# ECG.net
KiCad netlist of a schematic drawn in EAGLE
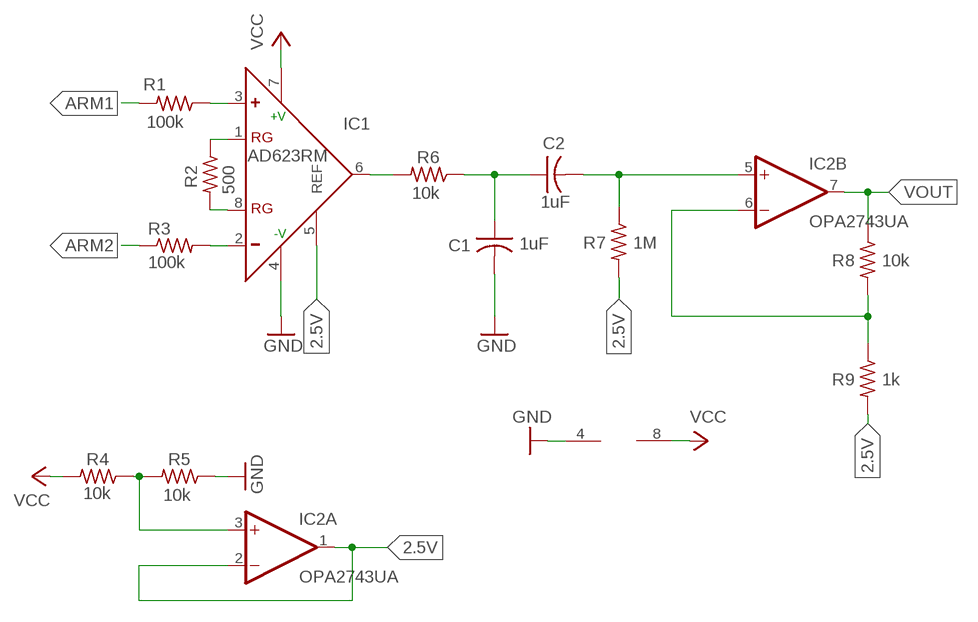
[diagram p0: schematic, sheet 1]

(export (version "E")
  (design (tool "Eeschema 10.0.6"))
  (components
    (comp (ref "C1")
      (value "1uF")
      (footprint "eagle-import:C0805")
      (libsource (lib "eagle-import") (part "C-USC0805"))
    )
    (comp (ref "C2")
      (value "1uF")
      (footprint "eagle-import:C0805")
      (libsource (lib "eagle-import") (part "C-USC0805"))
    )
    (comp (ref "IC1")
      (value "AD623RM")
      (footprint "eagle-import:MSOP08")
      (fields (field (name "MPN") "AD623ARMZ"))
      (libsource (lib "eagle-import") (part "AD623RM"))
    )
    (comp (ref "IC2")
      (value "OPA2743UA")
      (footprint "eagle-import:SOIC8")
      (libsource (lib "eagle-import") (part "OPA2743UA"))
    )
    (comp (ref "R1")
      (value "100k")
      (footprint "eagle-import:R0805")
      (libsource (lib "eagle-import") (part "R-US_R0805"))
    )
    (comp (ref "R2")
      (value "500")
      (footprint "eagle-import:R0805")
      (libsource (lib "eagle-import") (part "R-US_R0805"))
    )
    (comp (ref "R3")
      (value "100k")
      (footprint "eagle-import:R0805")
      (libsource (lib "eagle-import") (part "R-US_R0805"))
    )
    (comp (ref "R4")
      (value "10k")
      (footprint "eagle-import:R0805")
      (libsource (lib "eagle-import") (part "R-US_R0805"))
    )
    (comp (ref "R5")
      (value "10k")
      (footprint "eagle-import:R0805")
      (libsource (lib "eagle-import") (part "R-US_R0805"))
    )
    (comp (ref "R6")
      (value "10k")
      (footprint "eagle-import:R0805")
      (libsource (lib "eagle-import") (part "R-US_R0805"))
    )
    (comp (ref "R7")
      (value "1M")
      (footprint "eagle-import:R0805")
      (libsource (lib "eagle-import") (part "R-US_R0805"))
    )
    (comp (ref "R8")
      (value "10k")
      (footprint "eagle-import:R0805")
      (libsource (lib "eagle-import") (part "R-US_R0805"))
    )
    (comp (ref "R9")
      (value "1k")
      (footprint "eagle-import:R0805")
      (libsource (lib "eagle-import") (part "R-US_R0805"))
    )
  )
  (nets
    (net (code "1") (name "2.5V") (class "Default")
      (node (ref "IC1") (pin "5") (pinfunction "REF_5") (pintype "passive"))
      (node (ref "IC2") (pin "1") (pinfunction "OUT_1") (pintype "output"))
      (node (ref "IC2") (pin "2") (pinfunction "-IN_2") (pintype "input"))
      (node (ref "R7") (pin "2") (pinfunction "2_2") (pintype "passive"))
      (node (ref "R9") (pin "2") (pinfunction "2_2") (pintype "passive"))
    )
    (net (code "2") (name "ARM1") (class "Default")
      (node (ref "R1") (pin "2") (pinfunction "2_2") (pintype "passive"))
    )
    (net (code "3") (name "ARM2") (class "Default")
      (node (ref "R3") (pin "1") (pinfunction "1_1") (pintype "passive"))
    )
    (net (code "4") (name "GND") (class "Default")
      (node (ref "C1") (pin "2") (pinfunction "2_2") (pintype "passive"))
      (node (ref "IC1") (pin "4") (pinfunction "-V_4") (pintype "power_in"))
      (node (ref "IC2") (pin "4") (pinfunction "V-_4") (pintype "power_in"))
      (node (ref "R5") (pin "1") (pinfunction "1_1") (pintype "passive"))
    )
    (net (code "5") (name "Net-(C1-Pad1)") (class "Default")
      (node (ref "C1") (pin "1") (pinfunction "1_1") (pintype "passive"))
      (node (ref "C2") (pin "1") (pinfunction "1_1") (pintype "passive"))
      (node (ref "R6") (pin "1") (pinfunction "1_1") (pintype "passive"))
    )
    (net (code "6") (name "Net-(IC1-+)") (class "Default")
      (node (ref "IC1") (pin "3") (pinfunction "+_3") (pintype "input"))
      (node (ref "R1") (pin "1") (pinfunction "1_1") (pintype "passive"))
    )
    (net (code "7") (name "Net-(IC1--)") (class "Default")
      (node (ref "IC1") (pin "2") (pinfunction "-_2") (pintype "input"))
      (node (ref "R3") (pin "2") (pinfunction "2_2") (pintype "passive"))
    )
    (net (code "8") (name "Net-(IC1-OUT)") (class "Default")
      (node (ref "IC1") (pin "6") (pinfunction "OUT_6") (pintype "output"))
      (node (ref "R6") (pin "2") (pinfunction "2_2") (pintype "passive"))
    )
    (net (code "9") (name "Net-(IC1-RG-Pad1)") (class "Default")
      (node (ref "IC1") (pin "1") (pinfunction "RG_1") (pintype "passive"))
      (node (ref "R2") (pin "1") (pinfunction "1_1") (pintype "passive"))
    )
    (net (code "10") (name "Net-(IC1-RG-Pad8)") (class "Default")
      (node (ref "IC1") (pin "8") (pinfunction "RG_8") (pintype "passive"))
      (node (ref "R2") (pin "2") (pinfunction "2_2") (pintype "passive"))
    )
    (net (code "11") (name "Net-(IC2A-+IN)") (class "Default")
      (node (ref "IC2") (pin "3") (pinfunction "+IN_3") (pintype "input"))
      (node (ref "R4") (pin "1") (pinfunction "1_1") (pintype "passive"))
      (node (ref "R5") (pin "2") (pinfunction "2_2") (pintype "passive"))
    )
    (net (code "12") (name "Net-(IC2B-+IN)") (class "Default")
      (node (ref "C2") (pin "2") (pinfunction "2_2") (pintype "passive"))
      (node (ref "IC2") (pin "5") (pinfunction "+IN_5") (pintype "input"))
      (node (ref "R7") (pin "1") (pinfunction "1_1") (pintype "passive"))
    )
    (net (code "13") (name "Net-(IC2B--IN)") (class "Default")
      (node (ref "IC2") (pin "6") (pinfunction "-IN_6") (pintype "input"))
      (node (ref "R8") (pin "2") (pinfunction "2_2") (pintype "passive"))
      (node (ref "R9") (pin "1") (pinfunction "1_1") (pintype "passive"))
    )
    (net (code "14") (name "VCC") (class "Default")
      (node (ref "IC1") (pin "7") (pinfunction "+V_7") (pintype "power_in"))
      (node (ref "IC2") (pin "8") (pinfunction "V+_8") (pintype "power_in"))
      (node (ref "R4") (pin "2") (pinfunction "2_2") (pintype "passive"))
    )
    (net (code "15") (name "VOUT") (class "Default")
      (node (ref "IC2") (pin "7") (pinfunction "OUT_7") (pintype "output"))
      (node (ref "R8") (pin "1") (pinfunction "1_1") (pintype "passive"))
    )
  )
)
